# drone5.net
KiCad netlist of a schematic drawn in EAGLE
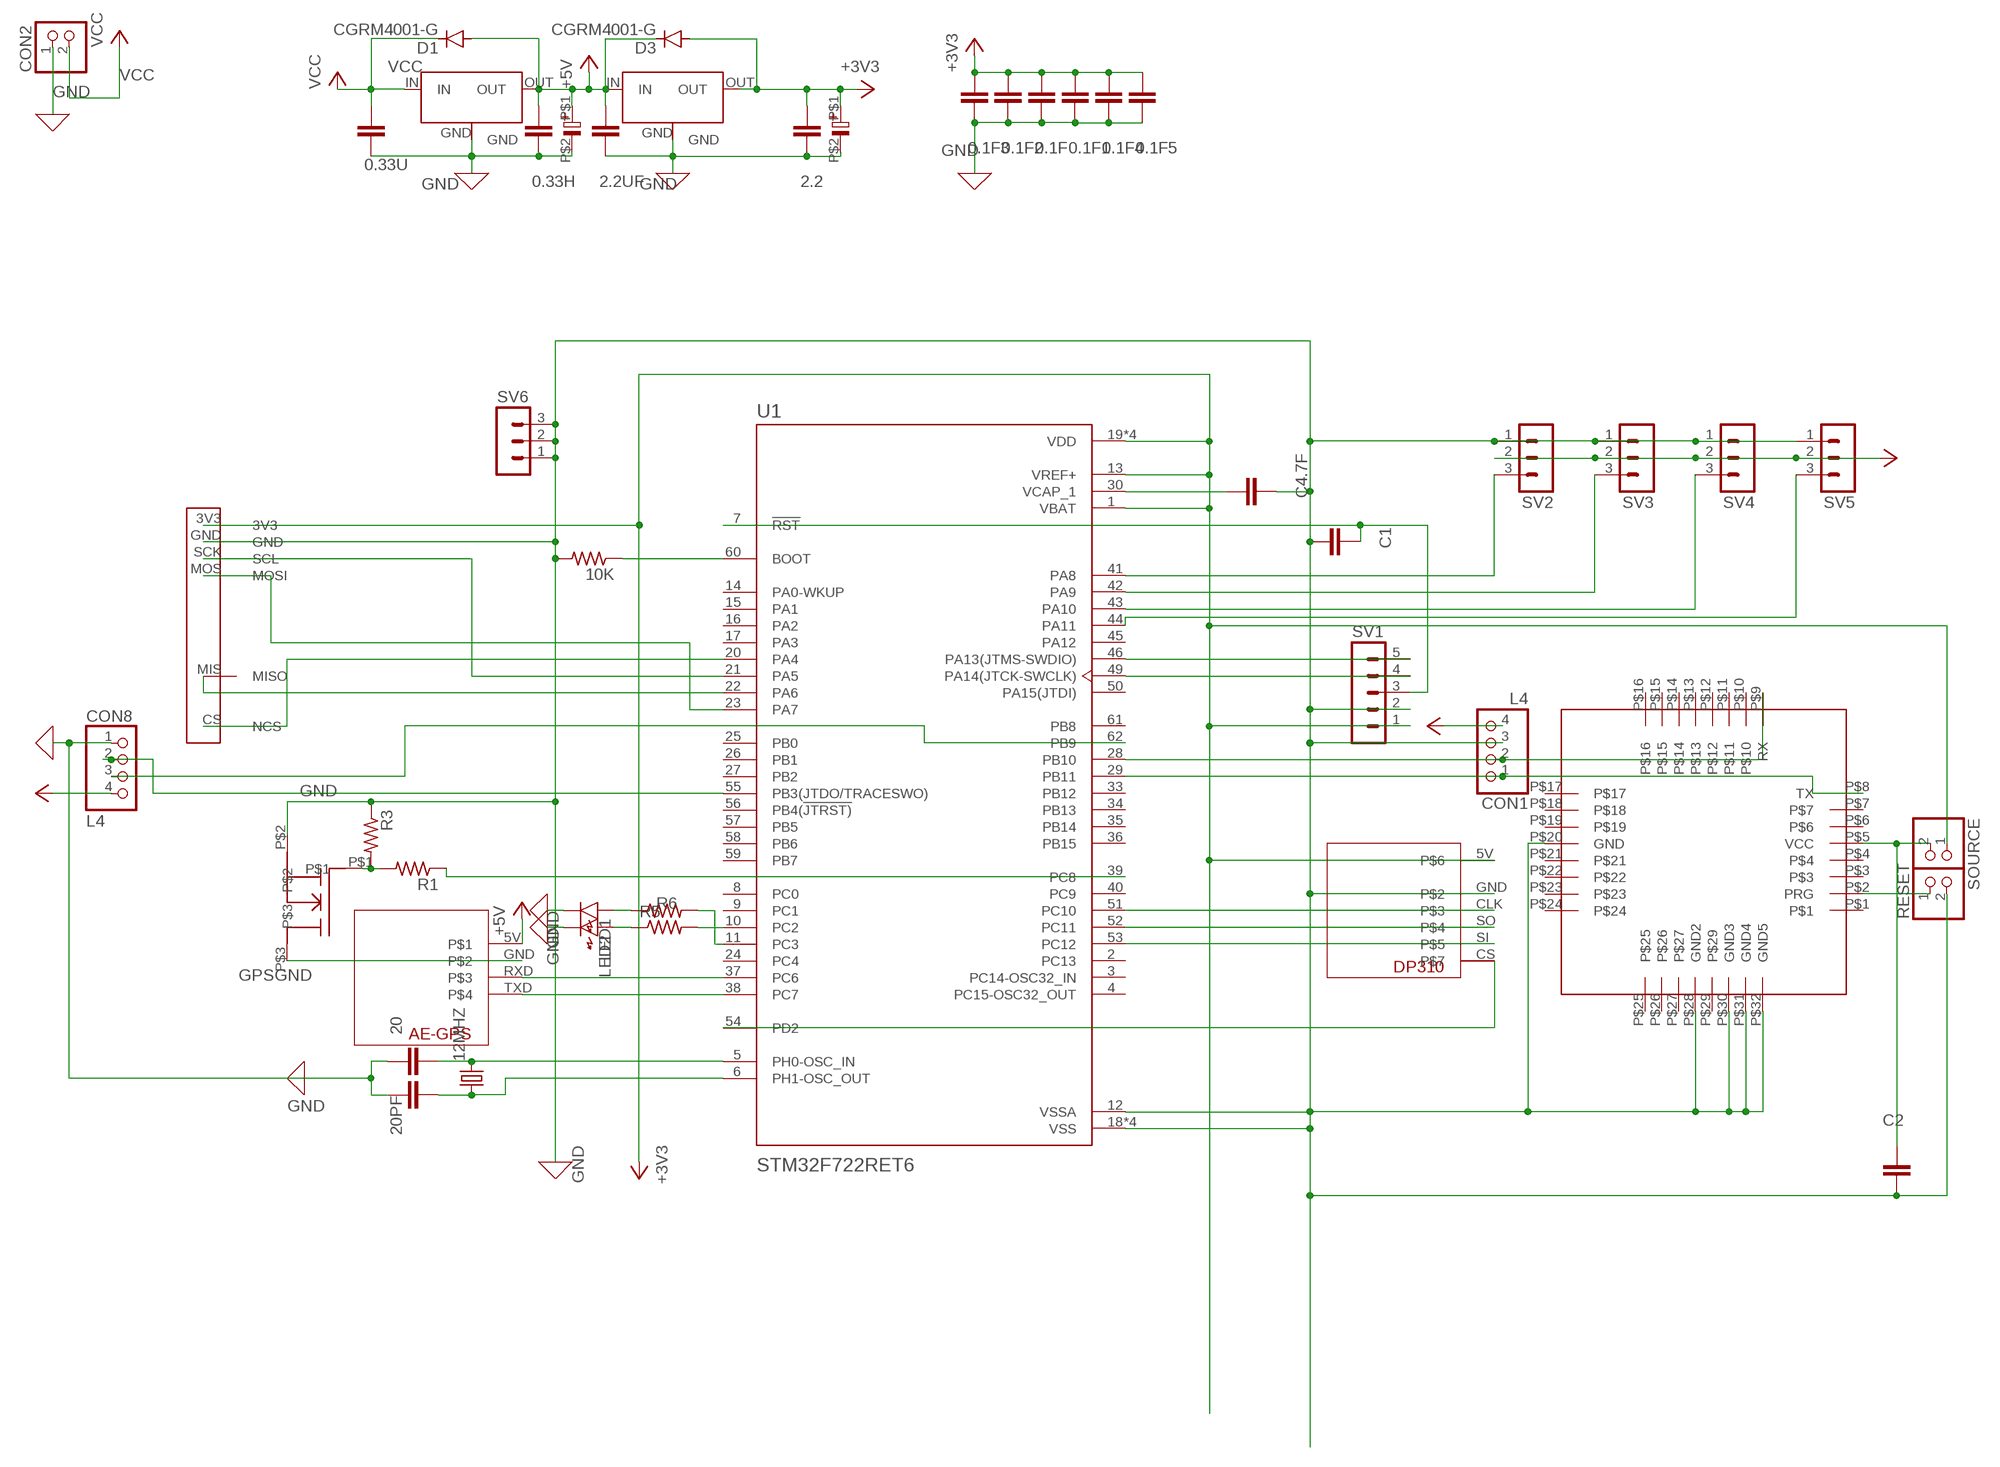
[diagram p0: schematic, sheet 1]

(export (version "E")
  (design (tool "Eeschema 10.0.6"))
  (components
    (comp (ref "0.1F")
      (value "C-EUC0603")
      (footprint "eagle-import:C0603")
      (libsource (lib "eagle-import") (part "C-EUC0603"))
    )
    (comp (ref "0.1F1")
      (value "C-EUC0603")
      (footprint "eagle-import:C0603")
      (libsource (lib "eagle-import") (part "C-EUC0603"))
    )
    (comp (ref "0.1F2")
      (value "C-EUC0603")
      (footprint "eagle-import:C0603")
      (libsource (lib "eagle-import") (part "C-EUC0603"))
    )
    (comp (ref "0.1F3")
      (value "C-EUC0603")
      (footprint "eagle-import:C0603")
      (libsource (lib "eagle-import") (part "C-EUC0603"))
    )
    (comp (ref "0.1F4")
      (value "C-EUC0603")
      (footprint "eagle-import:C0603")
      (libsource (lib "eagle-import") (part "C-EUC0603"))
    )
    (comp (ref "0.1F5")
      (value "C-EUC0603")
      (footprint "eagle-import:C0603")
      (libsource (lib "eagle-import") (part "C-EUC0603"))
    )
    (comp (ref "0.33H")
      (value "C-EUC0603")
      (footprint "eagle-import:C0603")
      (libsource (lib "eagle-import") (part "C-EUC0603"))
    )
    (comp (ref "0.33U")
      (value "C-EUC0603")
      (footprint "eagle-import:C0603")
      (libsource (lib "eagle-import") (part "C-EUC0603"))
    )
    (comp (ref "2.2")
      (value "C-EUC0603")
      (footprint "eagle-import:C0603")
      (libsource (lib "eagle-import") (part "C-EUC0603"))
    )
    (comp (ref "2.2UF")
      (value "C-EUC0603")
      (footprint "eagle-import:C0603")
      (libsource (lib "eagle-import") (part "C-EUC0603"))
    )
    (comp (ref "10K")
      (value "R-US_R0603")
      (footprint "eagle-import:R0603")
      (libsource (lib "eagle-import") (part "R-US_R0603"))
    )
    (comp (ref "12MHZ")
      (value "CRYSTALHC49S")
      (footprint "eagle-import:HC49_S")
      (fields (field (name "SPICEPREFIX") "B"))
      (libsource (lib "eagle-import") (part "CRYSTALHC49S"))
    )
    (comp (ref "20")
      (value "C-EUC0603")
      (footprint "eagle-import:C0603")
      (libsource (lib "eagle-import") (part "C-EUC0603"))
    )
    (comp (ref "20PF")
      (value "C-EUC0603")
      (footprint "eagle-import:C0603")
      (libsource (lib "eagle-import") (part "C-EUC0603"))
    )
    (comp (ref "47")
      (value "UCD0J470MCL1GS")
      (footprint "eagle-import:UCD0J470MCL1GS")
      (libsource (lib "eagle-import") (part "UCD0J470MCL1GS"))
    )
    (comp (ref "47U")
      (value "UCD0J470MCL1GS")
      (footprint "eagle-import:UCD0J470MCL1GS")
      (libsource (lib "eagle-import") (part "UCD0J470MCL1GS"))
    )
    (comp (ref "C1")
      (value "C-EUC0603")
      (footprint "eagle-import:C0603")
      (libsource (lib "eagle-import") (part "C-EUC0603"))
    )
    (comp (ref "C2")
      (value "C-EUC0603")
      (footprint "eagle-import:C0603")
      (libsource (lib "eagle-import") (part "C-EUC0603"))
    )
    (comp (ref "C4.7F")
      (value "C-EUC0603")
      (footprint "eagle-import:C0603")
      (libsource (lib "eagle-import") (part "C-EUC0603"))
    )
    (comp (ref "CON1")
      (value "L4")
      (footprint "eagle-import:L_4")
      (libsource (lib "eagle-import") (part "L4"))
    )
    (comp (ref "CON2")
      (value "L2")
      (footprint "eagle-import:L_2")
      (libsource (lib "eagle-import") (part "L2"))
    )
    (comp (ref "CON8")
      (value "L4")
      (footprint "eagle-import:L_4")
      (libsource (lib "eagle-import") (part "L4"))
    )
    (comp (ref "CS1")
      (value "DP310DP310")
      (footprint "eagle-import:AE-GPS-HOLE")
      (libsource (lib "eagle-import") (part "DP310DP310"))
    )
    (comp (ref "D1")
      (value "CGRM4001-G")
      (footprint "eagle-import:SOD-123_MINI-SMA")
      (libsource (lib "eagle-import") (part "CGRM400-G1"))
    )
    (comp (ref "D3")
      (value "CGRM4001-G")
      (footprint "eagle-import:SOD-123_MINI-SMA")
      (libsource (lib "eagle-import") (part "CGRM400-G1"))
    )
    (comp (ref "LED1")
      (value "LED1608")
      (footprint "eagle-import:LED1608")
      (libsource (lib "eagle-import") (part "LED1608"))
    )
    (comp (ref "LED2")
      (value "LED1608")
      (footprint "eagle-import:LED1608")
      (libsource (lib "eagle-import") (part "LED1608"))
    )
    (comp (ref "R1")
      (value "R-US_R0603")
      (footprint "eagle-import:R0603")
      (libsource (lib "eagle-import") (part "R-US_R0603"))
    )
    (comp (ref "R3")
      (value "R-US_R0603")
      (footprint "eagle-import:R0603")
      (libsource (lib "eagle-import") (part "R-US_R0603"))
    )
    (comp (ref "R5")
      (value "R-US_R0603")
      (footprint "eagle-import:R0603")
      (libsource (lib "eagle-import") (part "R-US_R0603"))
    )
    (comp (ref "R6")
      (value "R-US_R0603")
      (footprint "eagle-import:R0603")
      (libsource (lib "eagle-import") (part "R-US_R0603"))
    )
    (comp (ref "RESET")
      (value "PINHD-1X2")
      (footprint "eagle-import:1X02")
      (libsource (lib "eagle-import") (part "PINHD-1X2"))
    )
    (comp (ref "SOURCE")
      (value "PINHD-1X2")
      (footprint "eagle-import:1X02")
      (libsource (lib "eagle-import") (part "PINHD-1X2"))
    )
    (comp (ref "SV1")
      (value "MA05-1")
      (footprint "eagle-import:MA05-1")
      (libsource (lib "eagle-import") (part "MA05-1"))
    )
    (comp (ref "SV2")
      (value "MA03-1")
      (footprint "eagle-import:MA03-1")
      (libsource (lib "eagle-import") (part "MA03-1"))
    )
    (comp (ref "SV3")
      (value "MA03-1")
      (footprint "eagle-import:MA03-1")
      (libsource (lib "eagle-import") (part "MA03-1"))
    )
    (comp (ref "SV4")
      (value "MA03-1")
      (footprint "eagle-import:MA03-1")
      (libsource (lib "eagle-import") (part "MA03-1"))
    )
    (comp (ref "SV5")
      (value "MA03-1")
      (footprint "eagle-import:MA03-1")
      (libsource (lib "eagle-import") (part "MA03-1"))
    )
    (comp (ref "SV6")
      (value "MA03-1")
      (footprint "eagle-import:MA03-1")
      (libsource (lib "eagle-import") (part "MA03-1"))
    )
    (comp (ref "U$1")
      (value "LITE")
      (footprint "eagle-import:LITE")
      (libsource (lib "eagle-import") (part "LITE"))
    )
    (comp (ref "U$2")
      (value "MPU9250")
      (footprint "eagle-import:MPU9250")
      (libsource (lib "eagle-import") (part "MPU9250"))
    )
    (comp (ref "U$3")
      (value "AE-GPS-HOLE")
      (footprint "eagle-import:AE-GPS-HOLE")
      (libsource (lib "eagle-import") (part "AE-GPS-HOLE"))
    )
    (comp (ref "U$4")
      (value "NJM2391DL1-33")
      (footprint "eagle-import:NJM2391DL1-33")
      (libsource (lib "eagle-import") (part "NJM2391DL1-33"))
    )
    (comp (ref "U$7")
      (value "SSM3K329R")
      (footprint "eagle-import:SSM3K329R")
      (libsource (lib "eagle-import") (part "SSM3K329R"))
    )
    (comp (ref "U$9")
      (value "NJM2391DL1-33")
      (footprint "eagle-import:NJM2391DL1-33")
      (libsource (lib "eagle-import") (part "NJM2391DL1-33"))
    )
    (comp (ref "U1")
      (value "STM32F722RET6")
      (footprint "eagle-import:QFP50P1200X1200X160-64N")
      (fields (field (name "MF") "STMicroelectronics"))
      (libsource (lib "eagle-import") (part "STM32F722RET6"))
    )
  )
  (nets
    (net (code "1") (name "+3V3") (class "Default")
      (node (ref "0.1F") (pin "1") (pinfunction "1_1") (pintype "passive"))
      (node (ref "0.1F1") (pin "1") (pinfunction "1_1") (pintype "passive"))
      (node (ref "0.1F2") (pin "1") (pinfunction "1_1") (pintype "passive"))
      (node (ref "0.1F3") (pin "1") (pinfunction "1_1") (pintype "passive"))
      (node (ref "0.1F4") (pin "1") (pinfunction "1_1") (pintype "passive"))
      (node (ref "0.1F5") (pin "1") (pinfunction "1_1") (pintype "passive"))
      (node (ref "2.2") (pin "1") (pinfunction "1_1") (pintype "passive"))
      (node (ref "47") (pin "P$1") (pinfunction "+_P$1") (pintype "bidirectional"))
      (node (ref "CS1") (pin "5V") (pinfunction "P$6_5V") (pintype "bidirectional"))
      (node (ref "D3") (pin "A") (pinfunction "A_A") (pintype "passive"))
      (node (ref "SOURCE") (pin "1") (pinfunction "1_1") (pintype "passive"))
      (node (ref "SV1") (pin "1") (pinfunction "1_1") (pintype "passive"))
      (node (ref "U$2") (pin "3V3") (pinfunction "3V3_3V3") (pintype "bidirectional"))
      (node (ref "U$4") (pin "OUT") (pinfunction "OUT_OUT") (pintype "bidirectional"))
      (node (ref "U1") (pin "1") (pinfunction "VBAT_1") (pintype "power_in"))
      (node (ref "U1") (pin "13") (pinfunction "VREF+_13") (pintype "power_in"))
      (node (ref "U1") (pin "19") (pinfunction "VDD_19") (pintype "power_in"))
      (node (ref "U1") (pin "32") (pinfunction "VDD_32") (pintype "power_in"))
      (node (ref "U1") (pin "48") (pinfunction "VDD_48") (pintype "power_in"))
      (node (ref "U1") (pin "64") (pinfunction "VDD_64") (pintype "power_in"))
    )
    (net (code "2") (name "+5V") (class "Default")
      (node (ref "0.33H") (pin "1") (pinfunction "1_1") (pintype "passive"))
      (node (ref "2.2UF") (pin "1") (pinfunction "1_1") (pintype "passive"))
      (node (ref "47U") (pin "P$1") (pinfunction "+_P$1") (pintype "bidirectional"))
      (node (ref "CON1") (pin "4") (pinfunction "4_4") (pintype "passive"))
      (node (ref "CON8") (pin "4") (pinfunction "4_4") (pintype "passive"))
      (node (ref "D1") (pin "A") (pinfunction "A_A") (pintype "passive"))
      (node (ref "D3") (pin "C") (pinfunction "C_C") (pintype "passive"))
      (node (ref "SV2") (pin "2") (pinfunction "2_2") (pintype "passive"))
      (node (ref "SV3") (pin "2") (pinfunction "2_2") (pintype "passive"))
      (node (ref "SV4") (pin "2") (pinfunction "2_2") (pintype "passive"))
      (node (ref "SV5") (pin "2") (pinfunction "2_2") (pintype "passive"))
      (node (ref "U$3") (pin "5V") (pinfunction "P$1_5V") (pintype "bidirectional"))
      (node (ref "U$4") (pin "IN") (pinfunction "IN_IN") (pintype "bidirectional"))
      (node (ref "U$9") (pin "OUT") (pinfunction "OUT_OUT") (pintype "bidirectional"))
    )
    (net (code "3") (name "/GPSGND") (class "Default")
      (node (ref "U$3") (pin "GND") (pinfunction "P$2_GND") (pintype "bidirectional"))
      (node (ref "U$7") (pin "P$3") (pinfunction "P$3_P$3") (pintype "bidirectional"))
    )
    (net (code "4") (name "GND") (class "Default")
      (node (ref "0.1F") (pin "2") (pinfunction "2_2") (pintype "passive"))
      (node (ref "0.1F1") (pin "2") (pinfunction "2_2") (pintype "passive"))
      (node (ref "0.1F2") (pin "2") (pinfunction "2_2") (pintype "passive"))
      (node (ref "0.1F3") (pin "2") (pinfunction "2_2") (pintype "passive"))
      (node (ref "0.1F4") (pin "2") (pinfunction "2_2") (pintype "passive"))
      (node (ref "0.1F5") (pin "2") (pinfunction "2_2") (pintype "passive"))
      (node (ref "0.33H") (pin "2") (pinfunction "2_2") (pintype "passive"))
      (node (ref "0.33U") (pin "2") (pinfunction "2_2") (pintype "passive"))
      (node (ref "10K") (pin "2") (pinfunction "2_2") (pintype "passive"))
      (node (ref "2.2") (pin "2") (pinfunction "2_2") (pintype "passive"))
      (node (ref "2.2UF") (pin "2") (pinfunction "2_2") (pintype "passive"))
      (node (ref "20") (pin "1") (pinfunction "1_1") (pintype "passive"))
      (node (ref "20PF") (pin "1") (pinfunction "1_1") (pintype "passive"))
      (node (ref "47") (pin "P$2") (pinfunction "ー_P$2") (pintype "bidirectional"))
      (node (ref "47U") (pin "P$2") (pinfunction "ー_P$2") (pintype "bidirectional"))
      (node (ref "C1") (pin "1") (pinfunction "1_1") (pintype "passive"))
      (node (ref "C2") (pin "1") (pinfunction "1_1") (pintype "passive"))
      (node (ref "C4.7F") (pin "2") (pinfunction "2_2") (pintype "passive"))
      (node (ref "CON1") (pin "3") (pinfunction "3_3") (pintype "passive"))
      (node (ref "CON2") (pin "1") (pinfunction "GND_1") (pintype "passive"))
      (node (ref "CON8") (pin "1") (pinfunction "1_1") (pintype "passive"))
      (node (ref "CS1") (pin "GND") (pinfunction "P$2_GND") (pintype "bidirectional"))
      (node (ref "LED1") (pin "K") (pinfunction "K_K") (pintype "passive"))
      (node (ref "LED2") (pin "K") (pinfunction "K_K") (pintype "passive"))
      (node (ref "R3") (pin "1") (pinfunction "1_1") (pintype "passive"))
      (node (ref "RESET") (pin "2") (pinfunction "2_2") (pintype "passive"))
      (node (ref "SV1") (pin "2") (pinfunction "2_2") (pintype "passive"))
      (node (ref "SV2") (pin "1") (pinfunction "1_1") (pintype "passive"))
      (node (ref "SV3") (pin "1") (pinfunction "1_1") (pintype "passive"))
      (node (ref "SV4") (pin "1") (pinfunction "1_1") (pintype "passive"))
      (node (ref "SV5") (pin "1") (pinfunction "1_1") (pintype "passive"))
      (node (ref "SV6") (pin "1") (pinfunction "1_1") (pintype "passive"))
      (node (ref "SV6") (pin "2") (pinfunction "2_2") (pintype "passive"))
      (node (ref "SV6") (pin "3") (pinfunction "3_3") (pintype "passive"))
      (node (ref "U$1") (pin "P$20") (pinfunction "GND_P$20") (pintype "bidirectional"))
      (node (ref "U$1") (pin "P$28") (pinfunction "GND2_P$28") (pintype "bidirectional"))
      (node (ref "U$1") (pin "P$30") (pinfunction "GND3_P$30") (pintype "bidirectional"))
      (node (ref "U$1") (pin "P$31") (pinfunction "GND4_P$31") (pintype "bidirectional"))
      (node (ref "U$1") (pin "P$32") (pinfunction "GND5_P$32") (pintype "bidirectional"))
      (node (ref "U$2") (pin "GND") (pinfunction "GND_GND") (pintype "bidirectional"))
      (node (ref "U$4") (pin "GND") (pinfunction "GND_GND") (pintype "bidirectional"))
      (node (ref "U$7") (pin "P$2") (pinfunction "P$2_P$2") (pintype "bidirectional"))
      (node (ref "U$9") (pin "GND") (pinfunction "GND_GND") (pintype "bidirectional"))
      (node (ref "U1") (pin "12") (pinfunction "VSSA_12") (pintype "power_in"))
      (node (ref "U1") (pin "18") (pinfunction "VSS_18") (pintype "power_in"))
      (node (ref "U1") (pin "31") (pinfunction "VSS_31") (pintype "power_in"))
      (node (ref "U1") (pin "47") (pinfunction "VSS_47") (pintype "power_in"))
      (node (ref "U1") (pin "63") (pinfunction "VSS_63") (pintype "power_in"))
    )
    (net (code "5") (name "Net-(CS1-P$3)") (class "Default")
      (node (ref "CS1") (pin "CLK") (pinfunction "P$3_CLK") (pintype "bidirectional"))
      (node (ref "U1") (pin "51") (pinfunction "PC10_51") (pintype "bidirectional"))
    )
    (net (code "6") (name "Net-(CS1-P$4)") (class "Default")
      (node (ref "CS1") (pin "SO") (pinfunction "P$4_SO") (pintype "bidirectional"))
      (node (ref "U1") (pin "52") (pinfunction "PC11_52") (pintype "bidirectional"))
    )
    (net (code "7") (name "Net-(CS1-P$5)") (class "Default")
      (node (ref "CS1") (pin "SI") (pinfunction "P$5_SI") (pintype "bidirectional"))
      (node (ref "U1") (pin "53") (pinfunction "PC12_53") (pintype "bidirectional"))
    )
    (net (code "8") (name "Net-(CS1-P$7)") (class "Default")
      (node (ref "CS1") (pin "CS") (pinfunction "P$7_CS") (pintype "bidirectional"))
      (node (ref "U1") (pin "54") (pinfunction "PD2_54") (pintype "bidirectional"))
    )
    (net (code "9") (name "Net-(LED1-PadA)") (class "Default")
      (node (ref "LED1") (pin "A") (pinfunction "A_A") (pintype "passive"))
      (node (ref "R6") (pin "1") (pinfunction "1_1") (pintype "passive"))
    )
    (net (code "10") (name "Net-(LED2-PadA)") (class "Default")
      (node (ref "LED2") (pin "A") (pinfunction "A_A") (pintype "passive"))
      (node (ref "R5") (pin "1") (pinfunction "1_1") (pintype "passive"))
    )
    (net (code "11") (name "Net-(R1-Pad2)") (class "Default")
      (node (ref "R1") (pin "2") (pinfunction "2_2") (pintype "passive"))
      (node (ref "R3") (pin "2") (pinfunction "2_2") (pintype "passive"))
      (node (ref "U$7") (pin "P$1") (pinfunction "P$1_P$1") (pintype "bidirectional"))
    )
    (net (code "12") (name "Net-(U$1-PRG)") (class "Default")
      (node (ref "RESET") (pin "1") (pinfunction "1_1") (pintype "passive"))
      (node (ref "U$1") (pin "P$2") (pinfunction "PRG_P$2") (pintype "bidirectional"))
    )
    (net (code "13") (name "Net-(U$1-RX)") (class "Default")
      (node (ref "CON1") (pin "2") (pinfunction "2_2") (pintype "passive"))
      (node (ref "U$1") (pin "P$9") (pinfunction "RX_P$9") (pintype "bidirectional"))
      (node (ref "U1") (pin "28") (pinfunction "PB10_28") (pintype "bidirectional"))
    )
    (net (code "14") (name "Net-(U$1-TX)") (class "Default")
      (node (ref "CON1") (pin "1") (pinfunction "1_1") (pintype "passive"))
      (node (ref "U$1") (pin "P$8") (pinfunction "TX_P$8") (pintype "bidirectional"))
      (node (ref "U1") (pin "29") (pinfunction "PB11_29") (pintype "bidirectional"))
    )
    (net (code "15") (name "Net-(U$1-VCC)") (class "Default")
      (node (ref "C2") (pin "2") (pinfunction "2_2") (pintype "passive"))
      (node (ref "SOURCE") (pin "2") (pinfunction "2_2") (pintype "passive"))
      (node (ref "U$1") (pin "P$5") (pinfunction "VCC_P$5") (pintype "bidirectional"))
    )
    (net (code "16") (name "Net-(U$2-MISO)") (class "Default")
      (node (ref "U$2") (pin "MIS") (pinfunction "MISO_MIS") (pintype "bidirectional"))
      (node (ref "U1") (pin "22") (pinfunction "PA6_22") (pintype "bidirectional"))
    )
    (net (code "17") (name "Net-(U$2-MOSI)") (class "Default")
      (node (ref "U$2") (pin "MOS") (pinfunction "MOSI_MOS") (pintype "bidirectional"))
      (node (ref "U1") (pin "23") (pinfunction "PA7_23") (pintype "bidirectional"))
    )
    (net (code "18") (name "Net-(U$2-NCS)") (class "Default")
      (node (ref "U$2") (pin "CS") (pinfunction "NCS_CS") (pintype "bidirectional"))
      (node (ref "U1") (pin "20") (pinfunction "PA4_20") (pintype "bidirectional"))
    )
    (net (code "19") (name "Net-(U$2-SCL)") (class "Default")
      (node (ref "U$2") (pin "SCK") (pinfunction "SCL_SCK") (pintype "bidirectional"))
      (node (ref "U1") (pin "21") (pinfunction "PA5_21") (pintype "bidirectional"))
    )
    (net (code "20") (name "Net-(U$3-P$3)") (class "Default")
      (node (ref "U$3") (pin "RXD") (pinfunction "P$3_RXD") (pintype "bidirectional"))
      (node (ref "U1") (pin "37") (pinfunction "PC6_37") (pintype "bidirectional"))
    )
    (net (code "21") (name "Net-(U$3-P$4)") (class "Default")
      (node (ref "U$3") (pin "TXD") (pinfunction "P$4_TXD") (pintype "bidirectional"))
      (node (ref "U1") (pin "38") (pinfunction "PC7_38") (pintype "bidirectional"))
    )
    (net (code "22") (name "Net-(U1-BOOT)") (class "Default")
      (node (ref "10K") (pin "1") (pinfunction "1_1") (pintype "passive"))
      (node (ref "U1") (pin "60") (pinfunction "BOOT_60") (pintype "bidirectional"))
    )
    (net (code "23") (name "Net-(U1-PA8)") (class "Default")
      (node (ref "SV2") (pin "3") (pinfunction "3_3") (pintype "passive"))
      (node (ref "U1") (pin "41") (pinfunction "PA8_41") (pintype "bidirectional"))
    )
    (net (code "24") (name "Net-(U1-PA9)") (class "Default")
      (node (ref "SV3") (pin "3") (pinfunction "3_3") (pintype "passive"))
      (node (ref "U1") (pin "42") (pinfunction "PA9_42") (pintype "bidirectional"))
    )
    (net (code "25") (name "Net-(U1-PA10)") (class "Default")
      (node (ref "SV4") (pin "3") (pinfunction "3_3") (pintype "passive"))
      (node (ref "U1") (pin "43") (pinfunction "PA10_43") (pintype "bidirectional"))
    )
    (net (code "26") (name "Net-(U1-PA11)") (class "Default")
      (node (ref "SV5") (pin "3") (pinfunction "3_3") (pintype "passive"))
      (node (ref "U1") (pin "44") (pinfunction "PA11_44") (pintype "bidirectional"))
    )
    (net (code "27") (name "Net-(U1-PA13(JTMS-SWDIO))") (class "Default")
      (node (ref "SV1") (pin "5") (pinfunction "5_5") (pintype "passive"))
      (node (ref "U1") (pin "46") (pinfunction "PA13(JTMS-SWDIO)_46") (pintype "bidirectional"))
    )
    (net (code "28") (name "Net-(U1-PA14(JTCK-SWCLK))") (class "Default")
      (node (ref "SV1") (pin "4") (pinfunction "4_4") (pintype "passive"))
      (node (ref "U1") (pin "49") (pinfunction "PA14(JTCK-SWCLK)_49") (pintype "bidirectional"))
    )
    (net (code "29") (name "Net-(U1-PB3(JTDO{slash}TRACESWO))") (class "Default")
      (node (ref "CON8") (pin "2") (pinfunction "2_2") (pintype "passive"))
      (node (ref "U1") (pin "55") (pinfunction "PB3(JTDO/TRACESWO)_55") (pintype "bidirectional"))
    )
    (net (code "30") (name "Net-(U1-PB9)") (class "Default")
      (node (ref "CON8") (pin "3") (pinfunction "3_3") (pintype "passive"))
      (node (ref "U1") (pin "62") (pinfunction "PB9_62") (pintype "bidirectional"))
    )
    (net (code "31") (name "Net-(U1-PC2)") (class "Default")
      (node (ref "R5") (pin "2") (pinfunction "2_2") (pintype "passive"))
      (node (ref "U1") (pin "10") (pinfunction "PC2_10") (pintype "bidirectional"))
    )
    (net (code "32") (name "Net-(U1-PC3)") (class "Default")
      (node (ref "R6") (pin "2") (pinfunction "2_2") (pintype "passive"))
      (node (ref "U1") (pin "11") (pinfunction "PC3_11") (pintype "bidirectional"))
    )
    (net (code "33") (name "Net-(U1-PC8)") (class "Default")
      (node (ref "R1") (pin "1") (pinfunction "1_1") (pintype "passive"))
      (node (ref "U1") (pin "39") (pinfunction "PC8_39") (pintype "bidirectional"))
    )
    (net (code "34") (name "Net-(U1-PH0-OSC_IN)") (class "Default")
      (node (ref "12MHZ") (pin "2") (pinfunction "2_2") (pintype "passive"))
      (node (ref "20") (pin "2") (pinfunction "2_2") (pintype "passive"))
      (node (ref "U1") (pin "5") (pinfunction "PH0-OSC_IN_5") (pintype "bidirectional"))
    )
    (net (code "35") (name "Net-(U1-PH1-OSC_OUT)") (class "Default")
      (node (ref "12MHZ") (pin "1") (pinfunction "1_1") (pintype "passive"))
      (node (ref "20PF") (pin "2") (pinfunction "2_2") (pintype "passive"))
      (node (ref "U1") (pin "6") (pinfunction "PH1-OSC_OUT_6") (pintype "bidirectional"))
    )
    (net (code "36") (name "Net-(U1-VCAP_1)") (class "Default")
      (node (ref "C4.7F") (pin "1") (pinfunction "1_1") (pintype "passive"))
      (node (ref "U1") (pin "30") (pinfunction "VCAP_1_30") (pintype "power_in"))
    )
    (net (code "37") (name "Net-(U1-~{RST})") (class "Default")
      (node (ref "C1") (pin "2") (pinfunction "2_2") (pintype "passive"))
      (node (ref "SV1") (pin "3") (pinfunction "3_3") (pintype "passive"))
      (node (ref "U1") (pin "7") (pinfunction "~{RST}_7") (pintype "input"))
    )
    (net (code "38") (name "VCC") (class "Default")
      (node (ref "0.33U") (pin "1") (pinfunction "1_1") (pintype "passive"))
      (node (ref "CON2") (pin "2") (pinfunction "2_2") (pintype "passive"))
      (node (ref "D1") (pin "C") (pinfunction "C_C") (pintype "passive"))
      (node (ref "U$9") (pin "IN") (pinfunction "IN_IN") (pintype "bidirectional"))
    )
    (net (code "39") (name "unconnected-(U$1-PadP$1)") (class "Default")
      (node (ref "U$1") (pin "P$1") (pinfunction "P$1_P$1") (pintype "bidirectional"))
    )
    (net (code "40") (name "unconnected-(U$1-PadP$3)") (class "Default")
      (node (ref "U$1") (pin "P$3") (pinfunction "P$3_P$3") (pintype "bidirectional"))
    )
    (net (code "41") (name "unconnected-(U$1-PadP$4)") (class "Default")
      (node (ref "U$1") (pin "P$4") (pinfunction "P$4_P$4") (pintype "bidirectional"))
    )
    (net (code "42") (name "unconnected-(U$1-PadP$6)") (class "Default")
      (node (ref "U$1") (pin "P$6") (pinfunction "P$6_P$6") (pintype "bidirectional"))
    )
    (net (code "43") (name "unconnected-(U$1-PadP$7)") (class "Default")
      (node (ref "U$1") (pin "P$7") (pinfunction "P$7_P$7") (pintype "bidirectional"))
    )
    (net (code "44") (name "unconnected-(U$1-PadP$10)") (class "Default")
      (node (ref "U$1") (pin "P$10") (pinfunction "P$10_P$10") (pintype "bidirectional"))
    )
    (net (code "45") (name "unconnected-(U$1-PadP$11)") (class "Default")
      (node (ref "U$1") (pin "P$11") (pinfunction "P$11_P$11") (pintype "bidirectional"))
    )
    (net (code "46") (name "unconnected-(U$1-PadP$12)") (class "Default")
      (node (ref "U$1") (pin "P$12") (pinfunction "P$12_P$12") (pintype "bidirectional"))
    )
    (net (code "47") (name "unconnected-(U$1-PadP$13)") (class "Default")
      (node (ref "U$1") (pin "P$13") (pinfunction "P$13_P$13") (pintype "bidirectional"))
    )
    (net (code "48") (name "unconnected-(U$1-PadP$14)") (class "Default")
      (node (ref "U$1") (pin "P$14") (pinfunction "P$14_P$14") (pintype "bidirectional"))
    )
    (net (code "49") (name "unconnected-(U$1-PadP$15)") (class "Default")
      (node (ref "U$1") (pin "P$15") (pinfunction "P$15_P$15") (pintype "bidirectional"))
    )
    (net (code "50") (name "unconnected-(U$1-PadP$16)") (class "Default")
      (node (ref "U$1") (pin "P$16") (pinfunction "P$16_P$16") (pintype "bidirectional"))
    )
    (net (code "51") (name "unconnected-(U$1-PadP$17)") (class "Default")
      (node (ref "U$1") (pin "P$17") (pinfunction "P$17_P$17") (pintype "bidirectional"))
    )
    (net (code "52") (name "unconnected-(U$1-PadP$18)") (class "Default")
      (node (ref "U$1") (pin "P$18") (pinfunction "P$18_P$18") (pintype "bidirectional"))
    )
    (net (code "53") (name "unconnected-(U$1-PadP$19)") (class "Default")
      (node (ref "U$1") (pin "P$19") (pinfunction "P$19_P$19") (pintype "bidirectional"))
    )
    (net (code "54") (name "unconnected-(U$1-PadP$21)") (class "Default")
      (node (ref "U$1") (pin "P$21") (pinfunction "P$21_P$21") (pintype "bidirectional"))
    )
    (net (code "55") (name "unconnected-(U$1-PadP$22)") (class "Default")
      (node (ref "U$1") (pin "P$22") (pinfunction "P$22_P$22") (pintype "bidirectional"))
    )
    (net (code "56") (name "unconnected-(U$1-PadP$23)") (class "Default")
      (node (ref "U$1") (pin "P$23") (pinfunction "P$23_P$23") (pintype "bidirectional"))
    )
    (net (code "57") (name "unconnected-(U$1-PadP$24)") (class "Default")
      (node (ref "U$1") (pin "P$24") (pinfunction "P$24_P$24") (pintype "bidirectional"))
    )
    (net (code "58") (name "unconnected-(U$1-PadP$25)") (class "Default")
      (node (ref "U$1") (pin "P$25") (pinfunction "P$25_P$25") (pintype "bidirectional"))
    )
    (net (code "59") (name "unconnected-(U$1-PadP$26)") (class "Default")
      (node (ref "U$1") (pin "P$26") (pinfunction "P$26_P$26") (pintype "bidirectional"))
    )
    (net (code "60") (name "unconnected-(U$1-PadP$27)") (class "Default")
      (node (ref "U$1") (pin "P$27") (pinfunction "P$27_P$27") (pintype "bidirectional"))
    )
    (net (code "61") (name "unconnected-(U$1-PadP$29)") (class "Default")
      (node (ref "U$1") (pin "P$29") (pinfunction "P$29_P$29") (pintype "bidirectional"))
    )
    (net (code "62") (name "unconnected-(U1-PA0-WKUP-Pad14)") (class "Default")
      (node (ref "U1") (pin "14") (pinfunction "PA0-WKUP_14") (pintype "bidirectional"))
    )
    (net (code "63") (name "unconnected-(U1-PA1-Pad15)") (class "Default")
      (node (ref "U1") (pin "15") (pinfunction "PA1_15") (pintype "bidirectional"))
    )
    (net (code "64") (name "unconnected-(U1-PA2-Pad16)") (class "Default")
      (node (ref "U1") (pin "16") (pinfunction "PA2_16") (pintype "bidirectional"))
    )
    (net (code "65") (name "unconnected-(U1-PA3-Pad17)") (class "Default")
      (node (ref "U1") (pin "17") (pinfunction "PA3_17") (pintype "bidirectional"))
    )
    (net (code "66") (name "unconnected-(U1-PA12-Pad45)") (class "Default")
      (node (ref "U1") (pin "45") (pinfunction "PA12_45") (pintype "bidirectional"))
    )
    (net (code "67") (name "unconnected-(U1-PA15(JTDI)-Pad50)") (class "Default")
      (node (ref "U1") (pin "50") (pinfunction "PA15(JTDI)_50") (pintype "bidirectional"))
    )
    (net (code "68") (name "unconnected-(U1-PB0-Pad25)") (class "Default")
      (node (ref "U1") (pin "25") (pinfunction "PB0_25") (pintype "bidirectional"))
    )
    (net (code "69") (name "unconnected-(U1-PB1-Pad26)") (class "Default")
      (node (ref "U1") (pin "26") (pinfunction "PB1_26") (pintype "bidirectional"))
    )
    (net (code "70") (name "unconnected-(U1-PB2-Pad27)") (class "Default")
      (node (ref "U1") (pin "27") (pinfunction "PB2_27") (pintype "bidirectional"))
    )
    (net (code "71") (name "unconnected-(U1-PB4(~{JTRST})-Pad56)") (class "Default")
      (node (ref "U1") (pin "56") (pinfunction "PB4(~{JTRST})_56") (pintype "bidirectional"))
    )
    (net (code "72") (name "unconnected-(U1-PB5-Pad57)") (class "Default")
      (node (ref "U1") (pin "57") (pinfunction "PB5_57") (pintype "bidirectional"))
    )
    (net (code "73") (name "unconnected-(U1-PB6-Pad58)") (class "Default")
      (node (ref "U1") (pin "58") (pinfunction "PB6_58") (pintype "bidirectional"))
    )
    (net (code "74") (name "unconnected-(U1-PB7-Pad59)") (class "Default")
      (node (ref "U1") (pin "59") (pinfunction "PB7_59") (pintype "bidirectional"))
    )
    (net (code "75") (name "unconnected-(U1-PB8-Pad61)") (class "Default")
      (node (ref "U1") (pin "61") (pinfunction "PB8_61") (pintype "bidirectional"))
    )
    (net (code "76") (name "unconnected-(U1-PB12-Pad33)") (class "Default")
      (node (ref "U1") (pin "33") (pinfunction "PB12_33") (pintype "bidirectional"))
    )
    (net (code "77") (name "unconnected-(U1-PB13-Pad34)") (class "Default")
      (node (ref "U1") (pin "34") (pinfunction "PB13_34") (pintype "bidirectional"))
    )
    (net (code "78") (name "unconnected-(U1-PB14-Pad35)") (class "Default")
      (node (ref "U1") (pin "35") (pinfunction "PB14_35") (pintype "bidirectional"))
    )
    (net (code "79") (name "unconnected-(U1-PB15-Pad36)") (class "Default")
      (node (ref "U1") (pin "36") (pinfunction "PB15_36") (pintype "bidirectional"))
    )
    (net (code "80") (name "unconnected-(U1-PC0-Pad8)") (class "Default")
      (node (ref "U1") (pin "8") (pinfunction "PC0_8") (pintype "bidirectional"))
    )
    (net (code "81") (name "unconnected-(U1-PC1-Pad9)") (class "Default")
      (node (ref "U1") (pin "9") (pinfunction "PC1_9") (pintype "bidirectional"))
    )
    (net (code "82") (name "unconnected-(U1-PC4-Pad24)") (class "Default")
      (node (ref "U1") (pin "24") (pinfunction "PC4_24") (pintype "bidirectional"))
    )
    (net (code "83") (name "unconnected-(U1-PC9-Pad40)") (class "Default")
      (node (ref "U1") (pin "40") (pinfunction "PC9_40") (pintype "bidirectional"))
    )
    (net (code "84") (name "unconnected-(U1-PC13-Pad2)") (class "Default")
      (node (ref "U1") (pin "2") (pinfunction "PC13_2") (pintype "bidirectional"))
    )
    (net (code "85") (name "unconnected-(U1-PC14-OSC32_IN-Pad3)") (class "Default")
      (node (ref "U1") (pin "3") (pinfunction "PC14-OSC32_IN_3") (pintype "bidirectional"))
    )
    (net (code "86") (name "unconnected-(U1-PC15-OSC32_OUT-Pad4)") (class "Default")
      (node (ref "U1") (pin "4") (pinfunction "PC15-OSC32_OUT_4") (pintype "bidirectional"))
    )
  )
)
